# SplitterWaveyRadar.net
KiCad netlist of a schematic drawn in Altium Designer
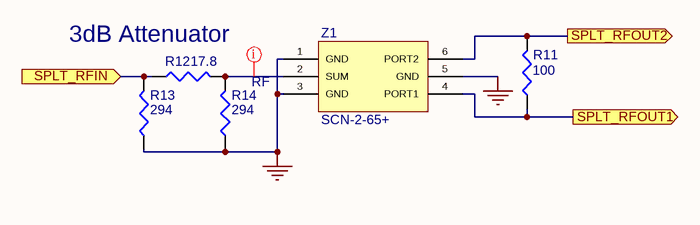
[diagram p0: SplitterWaveyRadar.SchDoc]

(export (version "E")
  (design (tool "Eeschema 10.0.6"))
  (components
    (comp (ref "R11")
      (value "100")
      (footprint "RESC0402(1005)_L")
      (description "Chip Resistor, 100 Ohms, +/-1 %, 63 mW, -55 to 155 degC, 0402")
      (fields (field (name "POWER") "63mW") (field (name "TOLERANCE") "1%"))
      (libsource (lib "University of South Florida") (part "RES-2"))
    )
    (comp (ref "R12")
      (value "17.8")
      (footprint "FP-CR0402-IPC_C")
      (description "Thick Film Resistors - SMD 17.8OHM 1/16WATT 1%")
      (fields (field (name "Comment") "CR0402-FX-17R8GLF"))
      (libsource (lib "University of South Florida") (part "ResistorSymbol"))
    )
    (comp (ref "R13")
      (value "294")
      (footprint "RESC1005X40X25NL05T10")
      (description "Res Thick Film 0402 294 Ohm 1% 1/16W 100ppm/C Molded SMD Paper T/R")
      (fields (field (name "Comment") "RC0402FR-07294RL"))
      (libsource (lib "University of South Florida") (part "ResistorSymbol"))
    )
    (comp (ref "R14")
      (value "294")
      (footprint "RESC1005X40X25NL05T10")
      (description "Res Thick Film 0402 294 Ohm 1% 1/16W 100ppm/C Molded SMD Paper T/R")
      (fields (field (name "Comment") "RC0402FR-07294RL"))
      (libsource (lib "University of South Florida") (part "ResistorSymbol"))
    )
    (comp (ref "Z1")
      (value "SCN-2-65+")
      (footprint "SCN-2-65+-Footprint-1")
      (description "2-Way 50 ohm Power Splitter/Combiner. 5500 to 6500MHz")
      (libsource (lib "University of South Florida") (part "SCN-2-65+"))
    )
  )
  (nets
    (net (code "1") (name "/SPLT_RFIN") (class "Default")
      (node (ref "R12") (pin "1") (pinfunction "1_1") (pintype "passive"))
      (node (ref "R13") (pin "2") (pinfunction "2_2") (pintype "passive"))
    )
    (net (code "2") (name "/SPLT_RFOUT1") (class "Default")
      (node (ref "R11") (pin "1") (pinfunction "1_1") (pintype "passive"))
      (node (ref "Z1") (pin "4") (pinfunction "PORT1_4") (pintype "passive"))
    )
    (net (code "3") (name "/SPLT_RFOUT2") (class "Default")
      (node (ref "R11") (pin "2") (pinfunction "2_2") (pintype "passive"))
      (node (ref "Z1") (pin "6") (pinfunction "PORT2_6") (pintype "passive"))
    )
    (net (code "4") (name "GND") (class "Default")
      (node (ref "R13") (pin "1") (pinfunction "1_1") (pintype "passive"))
      (node (ref "R14") (pin "1") (pinfunction "1_1") (pintype "passive"))
      (node (ref "Z1") (pin "1") (pinfunction "GND_1") (pintype "power_in"))
      (node (ref "Z1") (pin "3") (pinfunction "GND_3") (pintype "power_in"))
      (node (ref "Z1") (pin "5") (pinfunction "GND_5") (pintype "power_in"))
    )
    (net (code "5") (name "Net-(Z1-SUM)") (class "Default")
      (node (ref "R12") (pin "2") (pinfunction "2_2") (pintype "passive"))
      (node (ref "R14") (pin "2") (pinfunction "2_2") (pintype "passive"))
      (node (ref "Z1") (pin "2") (pinfunction "SUM_2") (pintype "passive"))
    )
  )
)
